# 5VPS.net
KiCad netlist of a schematic drawn in Altium Designer
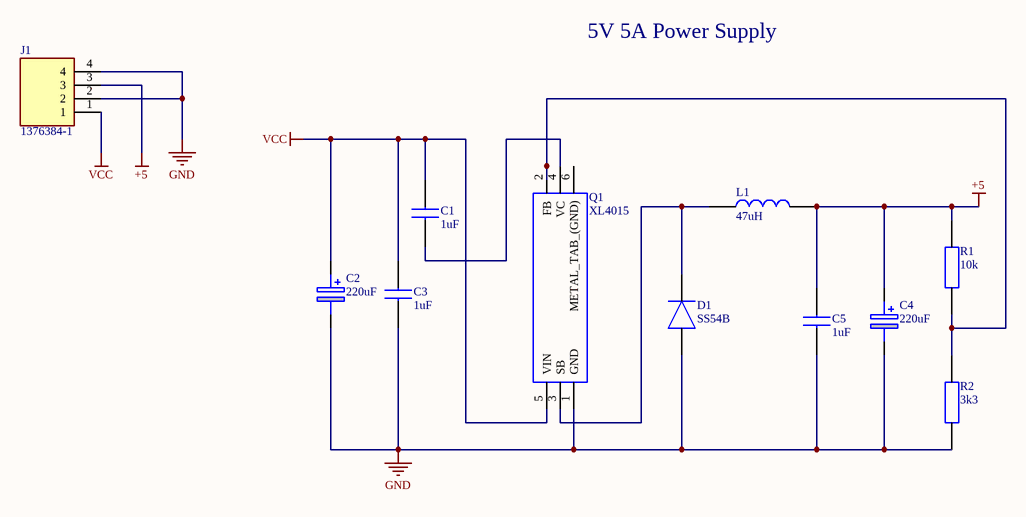
[diagram p0: 5VPS.SchDoc]

(export (version "E")
  (design (tool "Eeschema 10.0.6"))
  (components
    (comp (ref "C1")
      (value "1uF")
      (footprint "CAPC2012X145N")
      (description "Multilayer Ceramic Capacitors MLCC - SMD/SMT 0805 0.1uF 50volts X7R 5%")
      (fields (field (name "MANUFACTURER_PART_NUMBER") "GRM21BR71H104JA01L"))
      (libsource (lib "GRM21BR71H104JA01L") (part "GRM21BR71H104JA01L"))
    )
    (comp (ref "C2")
      (value "220uF")
      (footprint "FKV(K16)")
      (fields
        (field (name "MANUFACTURER_PART_NUMBER") "EEVFK2A221M")
        (field (name "RS PART NUMBER") "5370679")
      )
      (libsource (lib "EEVFK2A221M") (part "EEVFK2A221M"))
    )
    (comp (ref "C3")
      (value "1uF")
      (footprint "CAPC2012X145N")
      (description "Multilayer Ceramic Capacitors MLCC - SMD/SMT 0805 0.1uF 50volts X7R 5%")
      (fields (field (name "MANUFACTURER_PART_NUMBER") "GRM21BR71H104JA01L"))
      (libsource (lib "GRM21BR71H104JA01L") (part "GRM21BR71H104JA01L"))
    )
    (comp (ref "C4")
      (value "220uF")
      (footprint "FKV(K16)")
      (fields
        (field (name "MANUFACTURER_PART_NUMBER") "EEVFK2A221M")
        (field (name "RS PART NUMBER") "5370679")
      )
      (libsource (lib "EEVFK2A221M") (part "EEVFK2A221M"))
    )
    (comp (ref "C5")
      (value "1uF")
      (footprint "CAPC2012X145N")
      (description "Multilayer Ceramic Capacitors MLCC - SMD/SMT 0805 0.1uF 50volts X7R 5%")
      (fields (field (name "MANUFACTURER_PART_NUMBER") "GRM21BR71H104JA01L"))
      (libsource (lib "GRM21BR71H104JA01L") (part "GRM21BR71H104JA01L"))
    )
    (comp (ref "D1")
      (value "SS54B")
      (footprint "DIOM5336X244N")
      (description "HY Electronic Corp SS54B, SMT Rectifier Schottky Diode, 40V 5A, 2-Pin SMB")
      (fields (field (name "RS PART NUMBER") "1711461"))
      (libsource (lib "SS54B") (part "SS54B"))
    )
    (comp (ref "J1")
      (value "1376384-1")
      (footprint "TE_1376384-1")
      (description "4 Position Single Row 5 mm Pitch Pressfit Wire-Board Header Receptacle Assembly")
      (fields (field (name "MF") "TE Connectivity"))
      (libsource (lib "1376384-1") (part "1376384-1"))
    )
    (comp (ref "L1")
      (value "47uH")
      (footprint "INDPM110100X400N")
      (fields
        (field (name "MANUFACTURER_PART_NUMBER") "SRP1038A-470M")
        (field (name "RS PART NUMBER") "1728637")
      )
      (libsource (lib "SRP1038A-470M") (part "SRP1038A-470M"))
    )
    (comp (ref "Q1")
      (value "XL4015")
      (footprint "TO-263-5")
      (description "DC / DC converters in the housing TO263-5L, Voltage Regulator, Buck Converter, Switching Regulator")
      (fields (field (name "MANUFACTURER_PART_NUMBER") "AP1506-50K5G-13"))
      (libsource (lib "AP1506-50K5G-13") (part "AP1506-50K5G-13"))
    )
    (comp (ref "R1")
      (value "10k")
      (footprint "RESC2012X65N")
      (description "Thick Film Resistors - SMD 0805 510Kohm 1% High VoltageAEC-Q200")
      (fields (field (name "MANUFACTURER_PART_NUMBER") "KTR10EZPF5103"))
      (libsource (lib "KTR10EZPF5103") (part "KTR10EZPF5103"))
    )
    (comp (ref "R2")
      (value "3k3")
      (footprint "RESC2012X65N")
      (description "Thick Film Resistors - SMD 0805 510Kohm 1% High VoltageAEC-Q200")
      (fields (field (name "MANUFACTURER_PART_NUMBER") "KTR10EZPF5103"))
      (libsource (lib "KTR10EZPF5103") (part "KTR10EZPF5103"))
    )
  )
  (nets
    (net (code "1") (name "+5") (class "Default")
      (node (ref "C4") (pin "1") (pinfunction "+_1") (pintype "passive"))
      (node (ref "C5") (pin "2") (pinfunction "2_2") (pintype "passive"))
      (node (ref "J1") (pin "3") (pinfunction "3_3") (pintype "passive"))
      (node (ref "L1") (pin "2") (pinfunction "2_2") (pintype "passive"))
      (node (ref "R1") (pin "2") (pinfunction "2_2") (pintype "passive"))
    )
    (net (code "2") (name "GND") (class "Default")
      (node (ref "C2") (pin "2") (pinfunction "-_2") (pintype "passive"))
      (node (ref "C3") (pin "1") (pinfunction "1_1") (pintype "passive"))
      (node (ref "C4") (pin "2") (pinfunction "-_2") (pintype "passive"))
      (node (ref "C5") (pin "1") (pinfunction "1_1") (pintype "passive"))
      (node (ref "D1") (pin "2") (pinfunction "A_2") (pintype "passive"))
      (node (ref "J1") (pin "2") (pinfunction "2_2") (pintype "passive"))
      (node (ref "J1") (pin "4") (pinfunction "4_4") (pintype "passive"))
      (node (ref "Q1") (pin "1") (pinfunction "GND_1") (pintype "passive"))
      (node (ref "R2") (pin "1") (pinfunction "1_1") (pintype "passive"))
    )
    (net (code "3") (name "Net-(D1-K)") (class "Default")
      (node (ref "D1") (pin "1") (pinfunction "K_1") (pintype "passive"))
      (node (ref "L1") (pin "1") (pinfunction "1_1") (pintype "passive"))
      (node (ref "Q1") (pin "3") (pinfunction "SB_3") (pintype "passive"))
    )
    (net (code "4") (name "Net-(Q1-FB)") (class "Default")
      (node (ref "Q1") (pin "2") (pinfunction "FB_2") (pintype "passive"))
      (node (ref "R1") (pin "1") (pinfunction "1_1") (pintype "passive"))
      (node (ref "R2") (pin "2") (pinfunction "2_2") (pintype "passive"))
    )
    (net (code "5") (name "Net-(Q1-VC)") (class "Default")
      (node (ref "C1") (pin "1") (pinfunction "1_1") (pintype "passive"))
      (node (ref "Q1") (pin "4") (pinfunction "VC_4") (pintype "passive"))
    )
    (net (code "6") (name "VCC") (class "Default")
      (node (ref "C1") (pin "2") (pinfunction "2_2") (pintype "passive"))
      (node (ref "C2") (pin "1") (pinfunction "+_1") (pintype "passive"))
      (node (ref "C3") (pin "2") (pinfunction "2_2") (pintype "passive"))
      (node (ref "J1") (pin "1") (pinfunction "1_1") (pintype "passive"))
      (node (ref "Q1") (pin "5") (pinfunction "VIN_5") (pintype "passive"))
    )
    (net (code "7") (name "unconnected-(Q1-METAL_TAB_(GND)-Pad6)") (class "Default")
      (node (ref "Q1") (pin "6") (pinfunction "METAL_TAB_(GND)_6") (pintype "passive"))
    )
  )
)
